# schematic.net
KiCad netlist of a schematic drawn in EAGLE
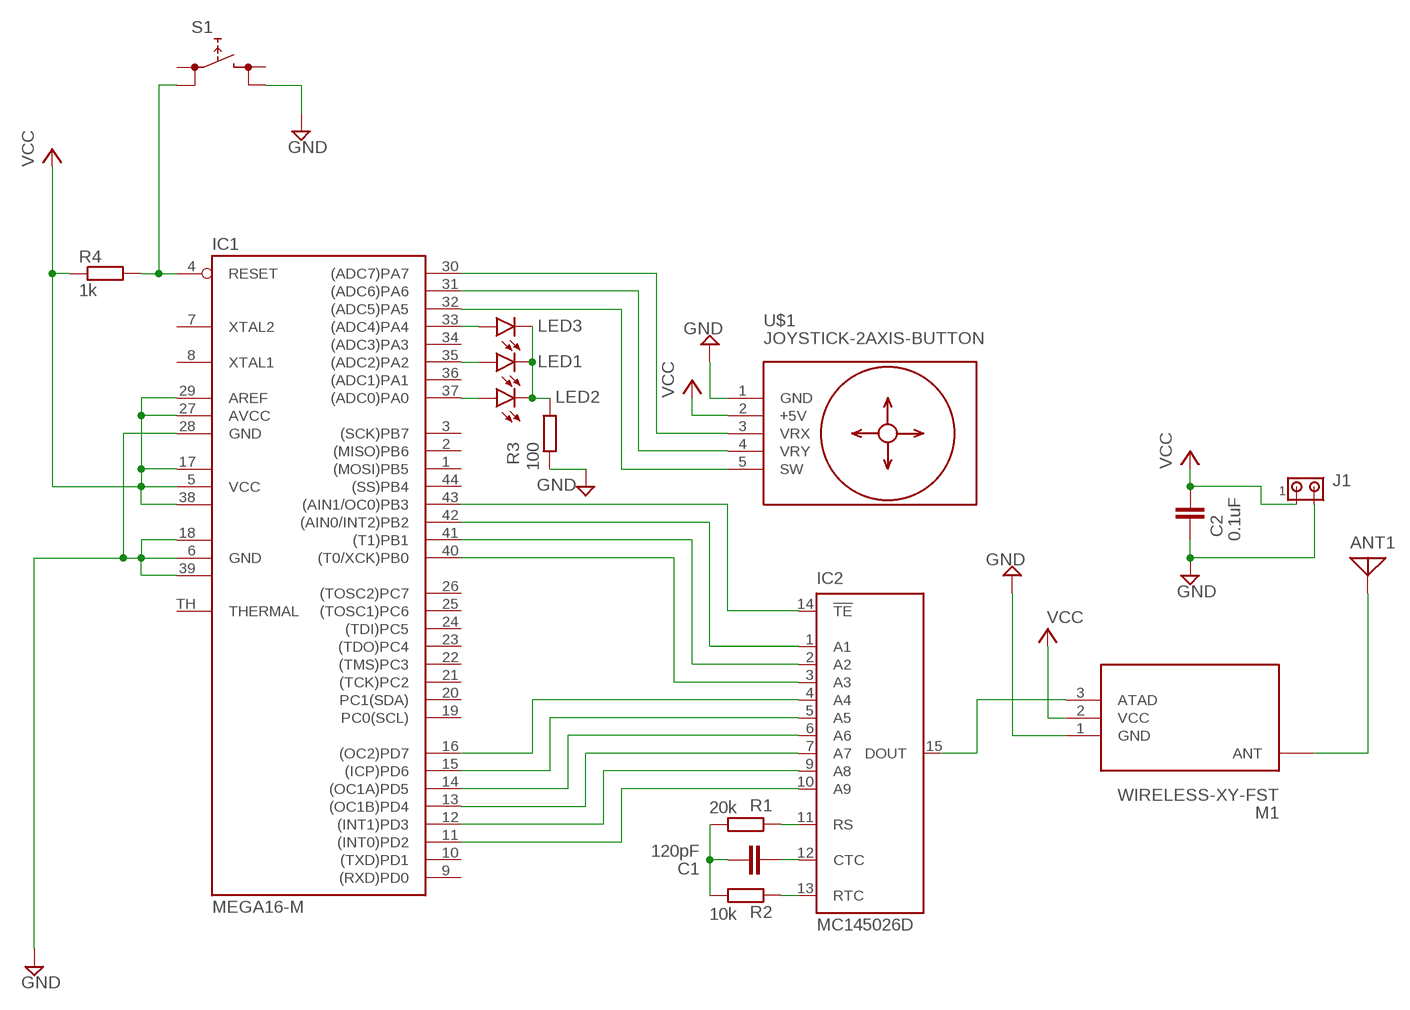
[diagram p0: schematic, sheet 1]

(export (version "E")
  (design (tool "Eeschema 10.0.6"))
  (components
    (comp (ref "ANT1")
      (value "ANTENNA")
      (footprint "eagle-import:PAD-01")
      (libsource (lib "eagle-import") (part "ANTENNA"))
    )
    (comp (ref "C1")
      (value "120pF")
      (footprint "eagle-import:C2.5-3")
      (libsource (lib "eagle-import") (part "C2,5-3"))
    )
    (comp (ref "C2")
      (value "0.1uF")
      (footprint "eagle-import:C2.5-3")
      (libsource (lib "eagle-import") (part "C2,5-3"))
    )
    (comp (ref "IC1")
      (value "MEGA16-M")
      (footprint "eagle-import:MLF44-TH")
      (fields (field (name "MPN") "ATMEGA16-16MU") (field (name "SPICEPREFIX") "X"))
      (libsource (lib "eagle-import") (part "MEGA16-M"))
    )
    (comp (ref "IC2")
      (value "MC145026D")
      (footprint "eagle-import:SO16")
      (libsource (lib "eagle-import") (part "MC145026D"))
    )
    (comp (ref "J1")
      (value "MTA02-100")
      (footprint "eagle-import:10X02MTA")
      (libsource (lib "eagle-import") (part "MTA02-100"))
    )
    (comp (ref "LED1")
      (value "LEDCHIPLED_1206")
      (footprint "eagle-import:CHIPLED_1206")
      (libsource (lib "eagle-import") (part "LEDCHIPLED_1206"))
    )
    (comp (ref "LED2")
      (value "LEDCHIPLED_1206")
      (footprint "eagle-import:CHIPLED_1206")
      (libsource (lib "eagle-import") (part "LEDCHIPLED_1206"))
    )
    (comp (ref "LED3")
      (value "LEDCHIPLED_1206")
      (footprint "eagle-import:CHIPLED_1206")
      (libsource (lib "eagle-import") (part "LEDCHIPLED_1206"))
    )
    (comp (ref "M1")
      (value "WIRELESS-XY-FST")
      (footprint "eagle-import:WIRELESS-XY-FST")
      (libsource (lib "eagle-import") (part "WIRELESS-XY-FST"))
    )
    (comp (ref "R1")
      (value "20k")
      (footprint "eagle-import:M0805")
      (libsource (lib "eagle-import") (part "R-EU_M0805"))
    )
    (comp (ref "R2")
      (value "10k")
      (footprint "eagle-import:R0805")
      (libsource (lib "eagle-import") (part "R-EU_R0805"))
    )
    (comp (ref "R3")
      (value "100")
      (footprint "eagle-import:M0805")
      (libsource (lib "eagle-import") (part "R-EU_M0805"))
    )
    (comp (ref "R4")
      (value "1k")
      (footprint "eagle-import:R0805")
      (libsource (lib "eagle-import") (part "R-EU_R0805"))
    )
    (comp (ref "S1")
      (value "REKN")
      (footprint "eagle-import:REKN")
      (libsource (lib "eagle-import") (part "REKN"))
    )
    (comp (ref "U$1")
      (value "JOYSTICK-2AXIS-BUTTON")
      (footprint "eagle-import:JOYSTICK-2AXIS-BUTTON")
      (libsource (lib "eagle-import") (part "JOYSTICK-2AXIS-BUTTON"))
    )
  )
  (nets
    (net (code "1") (name "GND") (class "Default")
      (node (ref "C2") (pin "1") (pinfunction "1_1") (pintype "passive"))
      (node (ref "IC1") (pin "18") (pinfunction "GND1_18") (pintype "power_in"))
      (node (ref "IC1") (pin "28") (pinfunction "GND_28") (pintype "power_in"))
      (node (ref "IC1") (pin "39") (pinfunction "GND2_39") (pintype "power_in"))
      (node (ref "IC1") (pin "6") (pinfunction "GND_6") (pintype "power_in"))
      (node (ref "J1") (pin "2") (pinfunction "2_2") (pintype "passive"))
      (node (ref "M1") (pin "1") (pinfunction "GND_1") (pintype "power_in"))
      (node (ref "R3") (pin "2") (pinfunction "2_2") (pintype "passive"))
      (node (ref "S1") (pin "1B") (pinfunction "1_1B") (pintype "passive"))
      (node (ref "U$1") (pin "1") (pinfunction "GND_1") (pintype "power_in"))
    )
    (net (code "2") (name "Net-(ANT1-Pad1)") (class "Default")
      (node (ref "ANT1") (pin "1") (pinfunction "1_1") (pintype "output"))
      (node (ref "M1") (pin "ANT") (pinfunction "ANT_ANT") (pintype "output"))
    )
    (net (code "3") (name "Net-(C1-Pad1)") (class "Default")
      (node (ref "C1") (pin "1") (pinfunction "1_1") (pintype "passive"))
      (node (ref "R1") (pin "2") (pinfunction "2_2") (pintype "passive"))
      (node (ref "R2") (pin "2") (pinfunction "2_2") (pintype "passive"))
    )
    (net (code "4") (name "Net-(IC1-(ADC0)PA0)") (class "Default")
      (node (ref "IC1") (pin "37") (pinfunction "(ADC0)PA0_37") (pintype "bidirectional"))
      (node (ref "LED2") (pin "A") (pinfunction "A_A") (pintype "passive"))
    )
    (net (code "5") (name "Net-(IC1-(ADC2)PA2)") (class "Default")
      (node (ref "IC1") (pin "35") (pinfunction "(ADC2)PA2_35") (pintype "bidirectional"))
      (node (ref "LED1") (pin "A") (pinfunction "A_A") (pintype "passive"))
    )
    (net (code "6") (name "Net-(IC1-(ADC4)PA4)") (class "Default")
      (node (ref "IC1") (pin "33") (pinfunction "(ADC4)PA4_33") (pintype "bidirectional"))
      (node (ref "LED3") (pin "A") (pinfunction "A_A") (pintype "passive"))
    )
    (net (code "7") (name "Net-(IC1-(ADC5)PA5)") (class "Default")
      (node (ref "IC1") (pin "32") (pinfunction "(ADC5)PA5_32") (pintype "bidirectional"))
      (node (ref "U$1") (pin "5") (pinfunction "SW_5") (pintype "passive"))
    )
    (net (code "8") (name "Net-(IC1-(ADC6)PA6)") (class "Default")
      (node (ref "IC1") (pin "31") (pinfunction "(ADC6)PA6_31") (pintype "bidirectional"))
      (node (ref "U$1") (pin "4") (pinfunction "VRY_4") (pintype "passive"))
    )
    (net (code "9") (name "Net-(IC1-(ADC7)PA7)") (class "Default")
      (node (ref "IC1") (pin "30") (pinfunction "(ADC7)PA7_30") (pintype "bidirectional"))
      (node (ref "U$1") (pin "3") (pinfunction "VRX_3") (pintype "passive"))
    )
    (net (code "10") (name "Net-(IC1-(AIN0{slash}INT2)PB2)") (class "Default")
      (node (ref "IC1") (pin "42") (pinfunction "(AIN0/INT2)PB2_42") (pintype "bidirectional"))
      (node (ref "IC2") (pin "1") (pinfunction "A1_1") (pintype "input"))
    )
    (net (code "11") (name "Net-(IC1-(AIN1{slash}OC0)PB3)") (class "Default")
      (node (ref "IC1") (pin "43") (pinfunction "(AIN1/OC0)PB3_43") (pintype "bidirectional"))
      (node (ref "IC2") (pin "14") (pinfunction "~{TE}_14") (pintype "input"))
    )
    (net (code "12") (name "Net-(IC1-(ICP)PD6)") (class "Default")
      (node (ref "IC1") (pin "15") (pinfunction "(ICP)PD6_15") (pintype "bidirectional"))
      (node (ref "IC2") (pin "5") (pinfunction "A5_5") (pintype "input"))
    )
    (net (code "13") (name "Net-(IC1-(INT0)PD2)") (class "Default")
      (node (ref "IC1") (pin "11") (pinfunction "(INT0)PD2_11") (pintype "bidirectional"))
      (node (ref "IC2") (pin "10") (pinfunction "A9_10") (pintype "input"))
    )
    (net (code "14") (name "Net-(IC1-(INT1)PD3)") (class "Default")
      (node (ref "IC1") (pin "12") (pinfunction "(INT1)PD3_12") (pintype "bidirectional"))
      (node (ref "IC2") (pin "9") (pinfunction "A8_9") (pintype "input"))
    )
    (net (code "15") (name "Net-(IC1-(OC1A)PD5)") (class "Default")
      (node (ref "IC1") (pin "14") (pinfunction "(OC1A)PD5_14") (pintype "bidirectional"))
      (node (ref "IC2") (pin "6") (pinfunction "A6_6") (pintype "input"))
    )
    (net (code "16") (name "Net-(IC1-(OC1B)PD4)") (class "Default")
      (node (ref "IC1") (pin "13") (pinfunction "(OC1B)PD4_13") (pintype "bidirectional"))
      (node (ref "IC2") (pin "7") (pinfunction "A7_7") (pintype "input"))
    )
    (net (code "17") (name "Net-(IC1-(OC2)PD7)") (class "Default")
      (node (ref "IC1") (pin "16") (pinfunction "(OC2)PD7_16") (pintype "bidirectional"))
      (node (ref "IC2") (pin "4") (pinfunction "A4_4") (pintype "input"))
    )
    (net (code "18") (name "Net-(IC1-(T0{slash}XCK)PB0)") (class "Default")
      (node (ref "IC1") (pin "40") (pinfunction "(T0/XCK)PB0_40") (pintype "bidirectional"))
      (node (ref "IC2") (pin "3") (pinfunction "A3_3") (pintype "input"))
    )
    (net (code "19") (name "Net-(IC1-(T1)PB1)") (class "Default")
      (node (ref "IC1") (pin "41") (pinfunction "(T1)PB1_41") (pintype "bidirectional"))
      (node (ref "IC2") (pin "2") (pinfunction "A2_2") (pintype "input"))
    )
    (net (code "20") (name "Net-(IC1-RESET)") (class "Default")
      (node (ref "IC1") (pin "4") (pinfunction "RESET_4") (pintype "input"))
      (node (ref "R4") (pin "2") (pinfunction "2_2") (pintype "passive"))
      (node (ref "S1") (pin "0B") (pinfunction "0_0B") (pintype "passive"))
    )
    (net (code "21") (name "Net-(IC2A-CTC)") (class "Default")
      (node (ref "C1") (pin "2") (pinfunction "2_2") (pintype "passive"))
      (node (ref "IC2") (pin "12") (pinfunction "CTC_12") (pintype "passive"))
    )
    (net (code "22") (name "Net-(IC2A-DOUT)") (class "Default")
      (node (ref "IC2") (pin "15") (pinfunction "DOUT_15") (pintype "input"))
      (node (ref "M1") (pin "3") (pinfunction "ATAD_3") (pintype "input"))
    )
    (net (code "23") (name "Net-(IC2A-RS)") (class "Default")
      (node (ref "IC2") (pin "11") (pinfunction "RS_11") (pintype "passive"))
      (node (ref "R1") (pin "1") (pinfunction "1_1") (pintype "passive"))
    )
    (net (code "24") (name "Net-(IC2A-RTC)") (class "Default")
      (node (ref "IC2") (pin "13") (pinfunction "RTC_13") (pintype "passive"))
      (node (ref "R2") (pin "1") (pinfunction "1_1") (pintype "passive"))
    )
    (net (code "25") (name "Net-(LED1-PadC)") (class "Default")
      (node (ref "LED1") (pin "C") (pinfunction "C_C") (pintype "passive"))
      (node (ref "LED2") (pin "C") (pinfunction "C_C") (pintype "passive"))
      (node (ref "LED3") (pin "C") (pinfunction "C_C") (pintype "passive"))
      (node (ref "R3") (pin "1") (pinfunction "1_1") (pintype "passive"))
    )
    (net (code "26") (name "VCC") (class "Default")
      (node (ref "C2") (pin "2") (pinfunction "2_2") (pintype "passive"))
      (node (ref "IC1") (pin "17") (pinfunction "VCC1_17") (pintype "power_in"))
      (node (ref "IC1") (pin "27") (pinfunction "AVCC_27") (pintype "power_in"))
      (node (ref "IC1") (pin "29") (pinfunction "AREF_29") (pintype "passive"))
      (node (ref "IC1") (pin "38") (pinfunction "VCC2_38") (pintype "power_in"))
      (node (ref "IC1") (pin "5") (pinfunction "VCC_5") (pintype "power_in"))
      (node (ref "J1") (pin "1") (pinfunction "1_1") (pintype "passive"))
      (node (ref "M1") (pin "2") (pinfunction "VCC_2") (pintype "power_in"))
      (node (ref "R4") (pin "1") (pinfunction "1_1") (pintype "passive"))
      (node (ref "U$1") (pin "2") (pinfunction "+5V_2") (pintype "power_in"))
    )
    (net (code "27") (name "unconnected-(IC1-(ADC1)PA1-Pad36)") (class "Default")
      (node (ref "IC1") (pin "36") (pinfunction "(ADC1)PA1_36") (pintype "bidirectional"))
    )
    (net (code "28") (name "unconnected-(IC1-(ADC3)PA3-Pad34)") (class "Default")
      (node (ref "IC1") (pin "34") (pinfunction "(ADC3)PA3_34") (pintype "bidirectional"))
    )
    (net (code "29") (name "unconnected-(IC1-(MISO)PB6-Pad2)") (class "Default")
      (node (ref "IC1") (pin "2") (pinfunction "(MISO)PB6_2") (pintype "bidirectional"))
    )
    (net (code "30") (name "unconnected-(IC1-(MOSI)PB5-Pad1)") (class "Default")
      (node (ref "IC1") (pin "1") (pinfunction "(MOSI)PB5_1") (pintype "bidirectional"))
    )
    (net (code "31") (name "unconnected-(IC1-(RXD)PD0-Pad9)") (class "Default")
      (node (ref "IC1") (pin "9") (pinfunction "(RXD)PD0_9") (pintype "bidirectional"))
    )
    (net (code "32") (name "unconnected-(IC1-(SCK)PB7-Pad3)") (class "Default")
      (node (ref "IC1") (pin "3") (pinfunction "(SCK)PB7_3") (pintype "bidirectional"))
    )
    (net (code "33") (name "unconnected-(IC1-(SS)PB4-Pad44)") (class "Default")
      (node (ref "IC1") (pin "44") (pinfunction "(SS)PB4_44") (pintype "bidirectional"))
    )
    (net (code "34") (name "unconnected-(IC1-(TCK)PC2-Pad21)") (class "Default")
      (node (ref "IC1") (pin "21") (pinfunction "(TCK)PC2_21") (pintype "bidirectional"))
    )
    (net (code "35") (name "unconnected-(IC1-(TDI)PC5-Pad24)") (class "Default")
      (node (ref "IC1") (pin "24") (pinfunction "(TDI)PC5_24") (pintype "bidirectional"))
    )
    (net (code "36") (name "unconnected-(IC1-(TDO)PC4-Pad23)") (class "Default")
      (node (ref "IC1") (pin "23") (pinfunction "(TDO)PC4_23") (pintype "bidirectional"))
    )
    (net (code "37") (name "unconnected-(IC1-(TMS)PC3-Pad22)") (class "Default")
      (node (ref "IC1") (pin "22") (pinfunction "(TMS)PC3_22") (pintype "bidirectional"))
    )
    (net (code "38") (name "unconnected-(IC1-(TOSC1)PC6-Pad25)") (class "Default")
      (node (ref "IC1") (pin "25") (pinfunction "(TOSC1)PC6_25") (pintype "bidirectional"))
    )
    (net (code "39") (name "unconnected-(IC1-(TOSC2)PC7-Pad26)") (class "Default")
      (node (ref "IC1") (pin "26") (pinfunction "(TOSC2)PC7_26") (pintype "bidirectional"))
    )
    (net (code "40") (name "unconnected-(IC1-(TXD)PD1-Pad10)") (class "Default")
      (node (ref "IC1") (pin "10") (pinfunction "(TXD)PD1_10") (pintype "bidirectional"))
    )
    (net (code "41") (name "unconnected-(IC1-PC0(SCL)-Pad19)") (class "Default")
      (node (ref "IC1") (pin "19") (pinfunction "PC0(SCL)_19") (pintype "bidirectional"))
    )
    (net (code "42") (name "unconnected-(IC1-PC1(SDA)-Pad20)") (class "Default")
      (node (ref "IC1") (pin "20") (pinfunction "PC1(SDA)_20") (pintype "bidirectional"))
    )
    (net (code "43") (name "unconnected-(IC1-THERMAL-PadTH)") (class "Default")
      (node (ref "IC1") (pin "TH") (pinfunction "THERMAL_TH") (pintype "input"))
    )
    (net (code "44") (name "unconnected-(IC1-XTAL1-Pad8)") (class "Default")
      (node (ref "IC1") (pin "8") (pinfunction "XTAL1_8") (pintype "bidirectional"))
    )
    (net (code "45") (name "unconnected-(IC1-XTAL2-Pad7)") (class "Default")
      (node (ref "IC1") (pin "7") (pinfunction "XTAL2_7") (pintype "bidirectional"))
    )
    (net (code "46") (name "unconnected-(S1-0-Pad0A)") (class "Default")
      (node (ref "S1") (pin "0A") (pinfunction "0_0A") (pintype "passive"))
    )
    (net (code "47") (name "unconnected-(S1-1-Pad1A)") (class "Default")
      (node (ref "S1") (pin "1A") (pinfunction "1_1A") (pintype "passive"))
    )
  )
)
